# rc_remote_switch.net
KiCad netlist of a schematic drawn in EAGLE
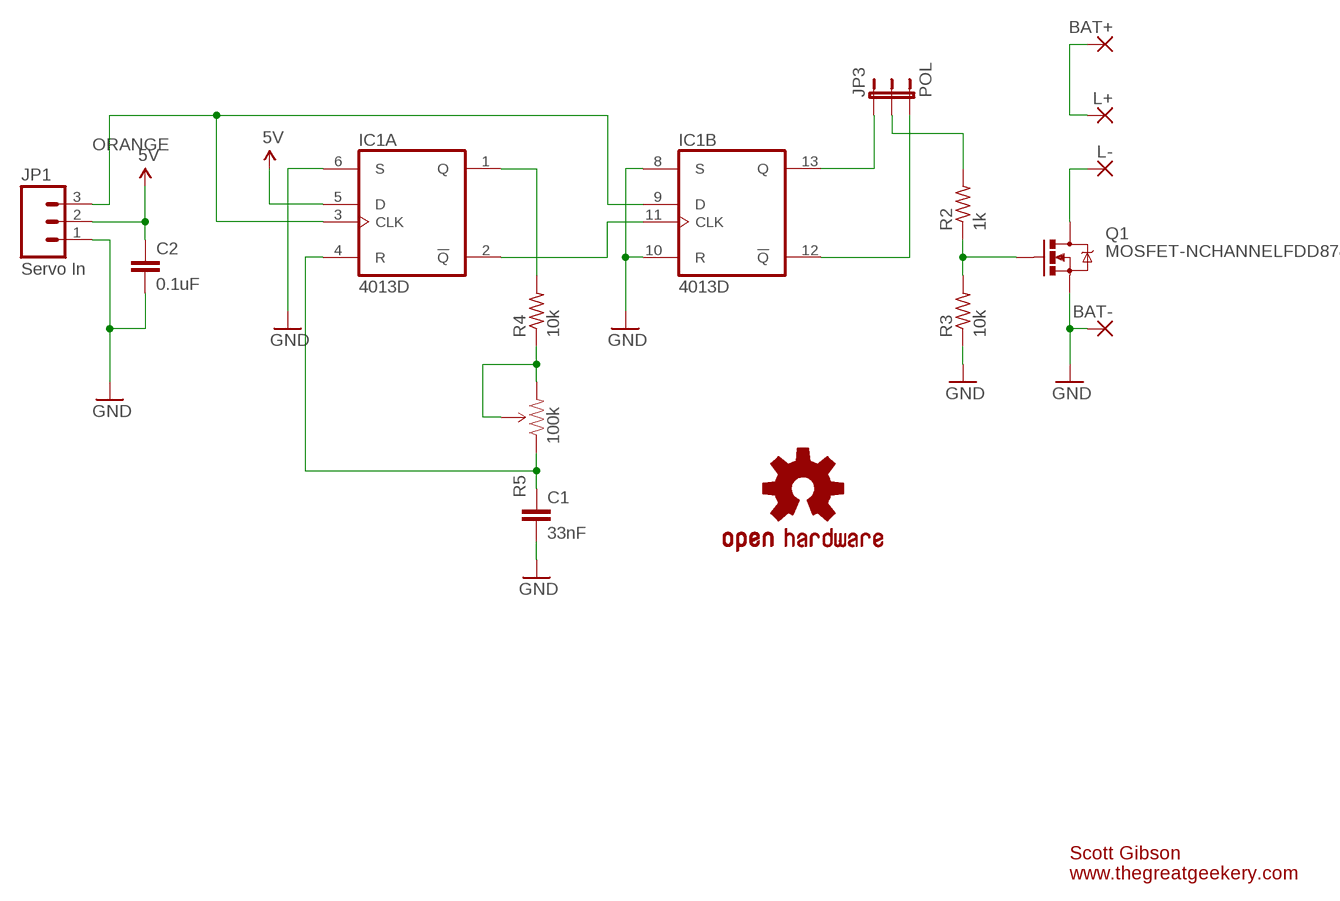
[diagram p0: schematic, sheet 1]

(export (version "E")
  (design (tool "Eeschema 10.0.6"))
  (components
    (comp (ref "BAT+")
      (value "BAT+")
      (footprint "eagle-import:4,16O1,6")
      (libsource (lib "eagle-import") (part "WIREPAD4,16O1,6"))
    )
    (comp (ref "BAT-")
      (value "BAT-")
      (footprint "eagle-import:4,16O1,6")
      (libsource (lib "eagle-import") (part "WIREPAD4,16O1,6"))
    )
    (comp (ref "C1")
      (value "33nF")
      (footprint "eagle-import:C0805")
      (libsource (lib "eagle-import") (part "C-EUC0805"))
    )
    (comp (ref "C2")
      (value "0.1uF")
      (footprint "eagle-import:C0805")
      (libsource (lib "eagle-import") (part "C-EUC0805"))
    )
    (comp (ref "IC1")
      (value "4013D")
      (footprint "eagle-import:SO14")
      (libsource (lib "eagle-import") (part "4013D"))
    )
    (comp (ref "JP1")
      (value "Servo In")
      (footprint "eagle-import:1X03")
      (libsource (lib "eagle-import") (part "M03PTH"))
    )
    (comp (ref "JP3")
      (value "POL")
      (footprint "eagle-import:1X03")
      (libsource (lib "eagle-import") (part "JUMPER-3PTH"))
    )
    (comp (ref "L+")
      (value "L+")
      (footprint "eagle-import:4,16O1,6")
      (libsource (lib "eagle-import") (part "WIREPAD4,16O1,6"))
    )
    (comp (ref "L-")
      (value "L-")
      (footprint "eagle-import:4,16O1,6")
      (libsource (lib "eagle-import") (part "WIREPAD4,16O1,6"))
    )
    (comp (ref "LOGO1")
      (value "OSHW-LOGOS")
      (footprint "eagle-import:OSHW-LOGO-S")
      (libsource (lib "eagle-import") (part "OSHW-LOGOS"))
    )
    (comp (ref "Q1")
      (value "MOSFET-NCHANNELFDD8780")
      (footprint "eagle-import:DPAK")
      (libsource (lib "eagle-import") (part "MOSFET-NCHANNELFDD8780"))
    )
    (comp (ref "R2")
      (value "1k")
      (footprint "eagle-import:R0805")
      (libsource (lib "eagle-import") (part "R-US_R0805"))
    )
    (comp (ref "R3")
      (value "10k")
      (footprint "eagle-import:R0805")
      (libsource (lib "eagle-import") (part "R-US_R0805"))
    )
    (comp (ref "R4")
      (value "10k")
      (footprint "eagle-import:R0805")
      (libsource (lib "eagle-import") (part "R-US_R0805"))
    )
    (comp (ref "R5")
      (value "100k")
      (footprint "eagle-import:3362U-2")
      (libsource (lib "eagle-import") (part "TRIMPOT3362U-2"))
    )
  )
  (nets
    (net (code "1") (name "/ORANGE") (class "Default")
      (node (ref "IC1") (pin "3") (pinfunction "CLK_3") (pintype "input"))
      (node (ref "IC1") (pin "9") (pinfunction "D_9") (pintype "input"))
      (node (ref "JP1") (pin "3") (pinfunction "3_3") (pintype "passive"))
    )
    (net (code "2") (name "5V") (class "Default")
      (node (ref "C2") (pin "1") (pinfunction "1_1") (pintype "passive"))
      (node (ref "IC1") (pin "5") (pinfunction "D_5") (pintype "input"))
      (node (ref "JP1") (pin "2") (pinfunction "2_2") (pintype "passive"))
    )
    (net (code "3") (name "GND") (class "Default")
      (node (ref "BAT-") (pin "1") (pinfunction "P_1") (pintype "passive"))
      (node (ref "C1") (pin "2") (pinfunction "2_2") (pintype "passive"))
      (node (ref "C2") (pin "2") (pinfunction "2_2") (pintype "passive"))
      (node (ref "IC1") (pin "10") (pinfunction "R_10") (pintype "input"))
      (node (ref "IC1") (pin "6") (pinfunction "S_6") (pintype "input"))
      (node (ref "IC1") (pin "8") (pinfunction "S_8") (pintype "input"))
      (node (ref "JP1") (pin "1") (pinfunction "1_1") (pintype "passive"))
      (node (ref "Q1") (pin "3") (pinfunction "S_3") (pintype "passive"))
      (node (ref "R3") (pin "1") (pinfunction "1_1") (pintype "passive"))
    )
    (net (code "4") (name "Net-(BAT+-P)") (class "Default")
      (node (ref "BAT+") (pin "1") (pinfunction "P_1") (pintype "passive"))
      (node (ref "L+") (pin "1") (pinfunction "P_1") (pintype "passive"))
    )
    (net (code "5") (name "Net-(IC1A-Q)") (class "Default")
      (node (ref "IC1") (pin "1") (pinfunction "Q_1") (pintype "output"))
      (node (ref "R4") (pin "2") (pinfunction "2_2") (pintype "passive"))
    )
    (net (code "6") (name "Net-(IC1A-R)") (class "Default")
      (node (ref "C1") (pin "1") (pinfunction "1_1") (pintype "passive"))
      (node (ref "IC1") (pin "4") (pinfunction "R_4") (pintype "input"))
      (node (ref "R5") (pin "1") (pinfunction "CCW_1") (pintype "passive"))
    )
    (net (code "7") (name "Net-(IC1A-~{Q})") (class "Default")
      (node (ref "IC1") (pin "11") (pinfunction "CLK_11") (pintype "input"))
      (node (ref "IC1") (pin "2") (pinfunction "~{Q}_2") (pintype "output"))
    )
    (net (code "8") (name "Net-(IC1B-Q)") (class "Default")
      (node (ref "IC1") (pin "13") (pinfunction "Q_13") (pintype "output"))
      (node (ref "JP3") (pin "1") (pinfunction "1_1") (pintype "passive"))
    )
    (net (code "9") (name "Net-(IC1B-~{Q})") (class "Default")
      (node (ref "IC1") (pin "12") (pinfunction "~{Q}_12") (pintype "output"))
      (node (ref "JP3") (pin "3") (pinfunction "3_3") (pintype "passive"))
    )
    (net (code "10") (name "Net-(JP3-Pad2)") (class "Default")
      (node (ref "JP3") (pin "2") (pinfunction "2_2") (pintype "passive"))
      (node (ref "R2") (pin "2") (pinfunction "2_2") (pintype "passive"))
    )
    (net (code "11") (name "Net-(L--P)") (class "Default")
      (node (ref "L-") (pin "1") (pinfunction "P_1") (pintype "passive"))
      (node (ref "Q1") (pin "4") (pinfunction "D_4") (pintype "passive"))
    )
    (net (code "12") (name "Net-(Q1-G)") (class "Default")
      (node (ref "Q1") (pin "1") (pinfunction "G_1") (pintype "passive"))
      (node (ref "R2") (pin "1") (pinfunction "1_1") (pintype "passive"))
      (node (ref "R3") (pin "2") (pinfunction "2_2") (pintype "passive"))
    )
    (net (code "13") (name "Net-(R5-CW)") (class "Default")
      (node (ref "R4") (pin "1") (pinfunction "1_1") (pintype "passive"))
      (node (ref "R5") (pin "2") (pinfunction "WIPER_2") (pintype "passive"))
      (node (ref "R5") (pin "3") (pinfunction "CW_3") (pintype "passive"))
    )
  )
)
